# Sheet1.net
KiCad netlist of a schematic drawn in Altium Designer
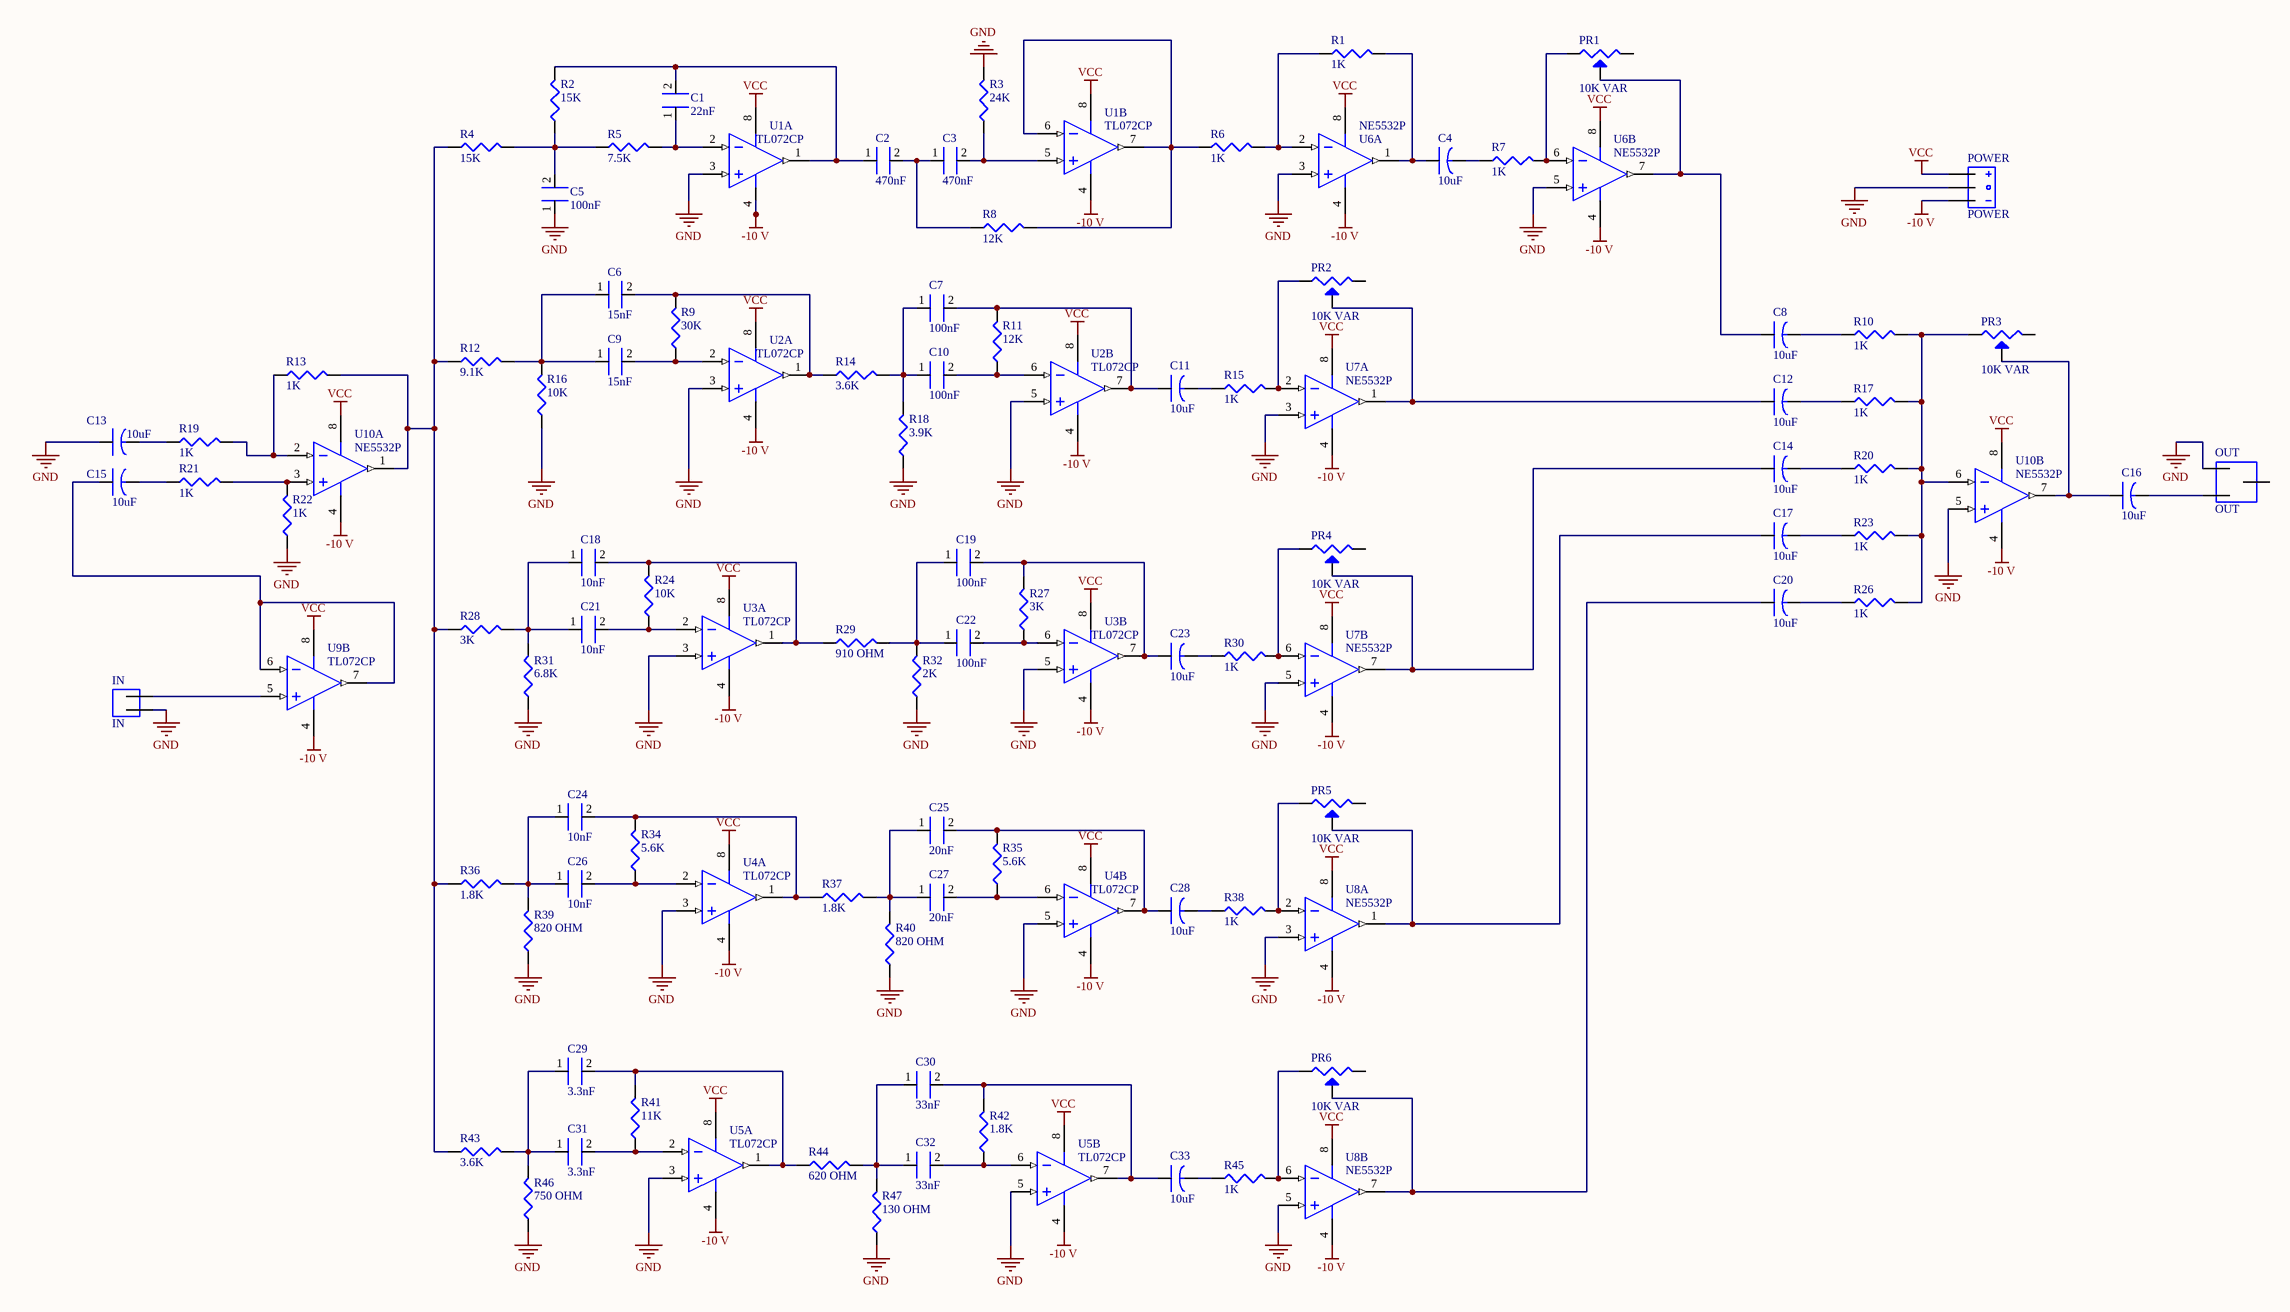
[diagram p0: Sheet1.SchDoc]

(export (version "E")
  (design (tool "Eeschema 10.0.6"))
  (components
    (comp (ref "C1")
      (value "22nF")
      (footprint "10nF")
      (fields
        (field (name "MANUFACTURER") "Nichicon")
        (field (name "MANUFACTURER PART NUMBER") "UKW1H0R1MDD1TD")
        (field (name "TOLERANCE") "20%")
      )
      (libsource (lib "Schlib1") (part "22nF"))
    )
    (comp (ref "C2")
      (value "470nF")
      (footprint "100nf")
      (fields
        (field (name "MANUFACTURER") "Nichicon")
        (field (name "MANUFACTURER PART NUMBER") "UKW1H0R1MDD1TD")
        (field (name "TOLERANCE") "20%")
      )
      (libsource (lib "Schlib1") (part "470nF"))
    )
    (comp (ref "C3")
      (value "470nF")
      (footprint "100nf")
      (fields
        (field (name "MANUFACTURER") "Nichicon")
        (field (name "MANUFACTURER PART NUMBER") "UKW1H0R1MDD1TD")
        (field (name "TOLERANCE") "20%")
      )
      (libsource (lib "Schlib1") (part "470nF"))
    )
    (comp (ref "C4")
      (value "10uF")
      (footprint "10uF")
      (description "YXF series 50V 10uF 5x11mm LS=2mm 105'C 10k HRS Aluminum Electrolytic Capacitor")
      (fields
        (field (name "MANUFACTURER") "Rubycon")
        (field (name "MANUFACTURER PART NUMBER") "50YXF10MEFC5X11")
      )
      (libsource (lib "Schlib1") (part "10uF"))
    )
    (comp (ref "C5")
      (value "100nF")
      (footprint "100nf")
      (fields
        (field (name "MANUFACTURER") "Nichicon")
        (field (name "MANUFACTURER PART NUMBER") "UKW1H0R1MDD1TD")
        (field (name "TOLERANCE") "20%")
      )
      (libsource (lib "Schlib1") (part "100nF"))
    )
    (comp (ref "C6")
      (value "15nF")
      (footprint "10nF")
      (fields
        (field (name "MANUFACTURER") "Nichicon")
        (field (name "MANUFACTURER PART NUMBER") "UKW1H0R1MDD1TD")
        (field (name "TOLERANCE") "20%")
      )
      (libsource (lib "Schlib1") (part "15nF"))
    )
    (comp (ref "C7")
      (value "100nF")
      (footprint "100nf")
      (fields
        (field (name "MANUFACTURER") "Nichicon")
        (field (name "MANUFACTURER PART NUMBER") "UKW1H0R1MDD1TD")
        (field (name "TOLERANCE") "20%")
      )
      (libsource (lib "Schlib1") (part "100nF"))
    )
    (comp (ref "C8")
      (value "10uF")
      (footprint "10uF")
      (description "YXF series 50V 10uF 5x11mm LS=2mm 105'C 10k HRS Aluminum Electrolytic Capacitor")
      (fields
        (field (name "MANUFACTURER") "Rubycon")
        (field (name "MANUFACTURER PART NUMBER") "50YXF10MEFC5X11")
      )
      (libsource (lib "Schlib1") (part "10uF"))
    )
    (comp (ref "C9")
      (value "15nF")
      (footprint "10nF")
      (fields
        (field (name "MANUFACTURER") "Nichicon")
        (field (name "MANUFACTURER PART NUMBER") "UKW1H0R1MDD1TD")
        (field (name "TOLERANCE") "20%")
      )
      (libsource (lib "Schlib1") (part "15nF"))
    )
    (comp (ref "C10")
      (value "100nF")
      (footprint "100nf")
      (fields
        (field (name "MANUFACTURER") "Nichicon")
        (field (name "MANUFACTURER PART NUMBER") "UKW1H0R1MDD1TD")
        (field (name "TOLERANCE") "20%")
      )
      (libsource (lib "Schlib1") (part "100nF"))
    )
    (comp (ref "C11")
      (value "10uF")
      (footprint "10uF")
      (description "YXF series 50V 10uF 5x11mm LS=2mm 105'C 10k HRS Aluminum Electrolytic Capacitor")
      (fields
        (field (name "MANUFACTURER") "Rubycon")
        (field (name "MANUFACTURER PART NUMBER") "50YXF10MEFC5X11")
      )
      (libsource (lib "Schlib1") (part "10uF"))
    )
    (comp (ref "C12")
      (value "10uF")
      (footprint "10uF")
      (description "YXF series 50V 10uF 5x11mm LS=2mm 105'C 10k HRS Aluminum Electrolytic Capacitor")
      (fields
        (field (name "MANUFACTURER") "Rubycon")
        (field (name "MANUFACTURER PART NUMBER") "50YXF10MEFC5X11")
      )
      (libsource (lib "Schlib1") (part "10uF"))
    )
    (comp (ref "C13")
      (value "10uF")
      (footprint "10uF")
      (description "YXF series 50V 10uF 5x11mm LS=2mm 105'C 10k HRS Aluminum Electrolytic Capacitor")
      (fields
        (field (name "MANUFACTURER") "Rubycon")
        (field (name "MANUFACTURER PART NUMBER") "50YXF10MEFC5X11")
      )
      (libsource (lib "Schlib1") (part "10uF"))
    )
    (comp (ref "C14")
      (value "10uF")
      (footprint "10uF")
      (description "YXF series 50V 10uF 5x11mm LS=2mm 105'C 10k HRS Aluminum Electrolytic Capacitor")
      (fields
        (field (name "MANUFACTURER") "Rubycon")
        (field (name "MANUFACTURER PART NUMBER") "50YXF10MEFC5X11")
      )
      (libsource (lib "Schlib1") (part "10uF"))
    )
    (comp (ref "C15")
      (value "10uF")
      (footprint "10uF")
      (description "YXF series 50V 10uF 5x11mm LS=2mm 105'C 10k HRS Aluminum Electrolytic Capacitor")
      (fields
        (field (name "MANUFACTURER") "Rubycon")
        (field (name "MANUFACTURER PART NUMBER") "50YXF10MEFC5X11")
      )
      (libsource (lib "Schlib1") (part "10uF"))
    )
    (comp (ref "C16")
      (value "10uF")
      (footprint "10uF")
      (description "YXF series 50V 10uF 5x11mm LS=2mm 105'C 10k HRS Aluminum Electrolytic Capacitor")
      (fields
        (field (name "MANUFACTURER") "Rubycon")
        (field (name "MANUFACTURER PART NUMBER") "50YXF10MEFC5X11")
      )
      (libsource (lib "Schlib1") (part "10uF"))
    )
    (comp (ref "C17")
      (value "10uF")
      (footprint "10uF")
      (description "YXF series 50V 10uF 5x11mm LS=2mm 105'C 10k HRS Aluminum Electrolytic Capacitor")
      (fields
        (field (name "MANUFACTURER") "Rubycon")
        (field (name "MANUFACTURER PART NUMBER") "50YXF10MEFC5X11")
      )
      (libsource (lib "Schlib1") (part "10uF"))
    )
    (comp (ref "C18")
      (value "10nF")
      (footprint "10nF")
      (fields
        (field (name "MANUFACTURER") "Nichicon")
        (field (name "MANUFACTURER PART NUMBER") "UKW1H0R1MDD1TD")
        (field (name "TOLERANCE") "20%")
      )
      (libsource (lib "Schlib1") (part "10nF"))
    )
    (comp (ref "C19")
      (value "100nF")
      (footprint "100nf")
      (fields
        (field (name "MANUFACTURER") "Nichicon")
        (field (name "MANUFACTURER PART NUMBER") "UKW1H0R1MDD1TD")
        (field (name "TOLERANCE") "20%")
      )
      (libsource (lib "Schlib1") (part "100nF"))
    )
    (comp (ref "C20")
      (value "10uF")
      (footprint "10uF")
      (description "YXF series 50V 10uF 5x11mm LS=2mm 105'C 10k HRS Aluminum Electrolytic Capacitor")
      (fields
        (field (name "MANUFACTURER") "Rubycon")
        (field (name "MANUFACTURER PART NUMBER") "50YXF10MEFC5X11")
      )
      (libsource (lib "Schlib1") (part "10uF"))
    )
    (comp (ref "C21")
      (value "10nF")
      (footprint "10nF")
      (fields
        (field (name "MANUFACTURER") "Nichicon")
        (field (name "MANUFACTURER PART NUMBER") "UKW1H0R1MDD1TD")
        (field (name "TOLERANCE") "20%")
      )
      (libsource (lib "Schlib1") (part "10nF"))
    )
    (comp (ref "C22")
      (value "100nF")
      (footprint "100nf")
      (fields
        (field (name "MANUFACTURER") "Nichicon")
        (field (name "MANUFACTURER PART NUMBER") "UKW1H0R1MDD1TD")
        (field (name "TOLERANCE") "20%")
      )
      (libsource (lib "Schlib1") (part "100nF"))
    )
    (comp (ref "C23")
      (value "10uF")
      (footprint "10uF")
      (description "YXF series 50V 10uF 5x11mm LS=2mm 105'C 10k HRS Aluminum Electrolytic Capacitor")
      (fields
        (field (name "MANUFACTURER") "Rubycon")
        (field (name "MANUFACTURER PART NUMBER") "50YXF10MEFC5X11")
      )
      (libsource (lib "Schlib1") (part "10uF"))
    )
    (comp (ref "C24")
      (value "10nF")
      (footprint "10nF")
      (fields
        (field (name "MANUFACTURER") "Nichicon")
        (field (name "MANUFACTURER PART NUMBER") "UKW1H0R1MDD1TD")
        (field (name "TOLERANCE") "20%")
      )
      (libsource (lib "Schlib1") (part "10nF"))
    )
    (comp (ref "C25")
      (value "20nF")
      (footprint "10nF")
      (fields
        (field (name "MANUFACTURER") "Nichicon")
        (field (name "MANUFACTURER PART NUMBER") "UKW1H0R1MDD1TD")
        (field (name "TOLERANCE") "20%")
      )
      (libsource (lib "Schlib1") (part "20nF"))
    )
    (comp (ref "C26")
      (value "10nF")
      (footprint "10nF")
      (fields
        (field (name "MANUFACTURER") "Nichicon")
        (field (name "MANUFACTURER PART NUMBER") "UKW1H0R1MDD1TD")
        (field (name "TOLERANCE") "20%")
      )
      (libsource (lib "Schlib1") (part "10nF"))
    )
    (comp (ref "C27")
      (value "20nF")
      (footprint "10nF")
      (fields
        (field (name "MANUFACTURER") "Nichicon")
        (field (name "MANUFACTURER PART NUMBER") "UKW1H0R1MDD1TD")
        (field (name "TOLERANCE") "20%")
      )
      (libsource (lib "Schlib1") (part "20nF"))
    )
    (comp (ref "C28")
      (value "10uF")
      (footprint "10uF")
      (description "YXF series 50V 10uF 5x11mm LS=2mm 105'C 10k HRS Aluminum Electrolytic Capacitor")
      (fields
        (field (name "MANUFACTURER") "Rubycon")
        (field (name "MANUFACTURER PART NUMBER") "50YXF10MEFC5X11")
      )
      (libsource (lib "Schlib1") (part "10uF"))
    )
    (comp (ref "C29")
      (value "3.3nF")
      (footprint "10nF")
      (fields
        (field (name "MANUFACTURER") "Nichicon")
        (field (name "MANUFACTURER PART NUMBER") "UKW1H0R1MDD1TD")
        (field (name "TOLERANCE") "20%")
      )
      (libsource (lib "Schlib1") (part "3.3nF"))
    )
    (comp (ref "C30")
      (value "33nF")
      (footprint "10nF")
      (fields
        (field (name "MANUFACTURER") "Nichicon")
        (field (name "MANUFACTURER PART NUMBER") "UKW1H0R1MDD1TD")
        (field (name "TOLERANCE") "20%")
      )
      (libsource (lib "Schlib1") (part "33nF"))
    )
    (comp (ref "C31")
      (value "3.3nF")
      (footprint "10nF")
      (fields
        (field (name "MANUFACTURER") "Nichicon")
        (field (name "MANUFACTURER PART NUMBER") "UKW1H0R1MDD1TD")
        (field (name "TOLERANCE") "20%")
      )
      (libsource (lib "Schlib1") (part "3.3nF"))
    )
    (comp (ref "C32")
      (value "33nF")
      (footprint "10nF")
      (fields
        (field (name "MANUFACTURER") "Nichicon")
        (field (name "MANUFACTURER PART NUMBER") "UKW1H0R1MDD1TD")
        (field (name "TOLERANCE") "20%")
      )
      (libsource (lib "Schlib1") (part "33nF"))
    )
    (comp (ref "C33")
      (value "10uF")
      (footprint "10uF")
      (description "YXF series 50V 10uF 5x11mm LS=2mm 105'C 10k HRS Aluminum Electrolytic Capacitor")
      (fields
        (field (name "MANUFACTURER") "Rubycon")
        (field (name "MANUFACTURER PART NUMBER") "50YXF10MEFC5X11")
      )
      (libsource (lib "Schlib1") (part "10uF"))
    )
    (comp (ref "IN") (value "IN") (footprint "AUDIO_IN") (libsource (lib "Schlib1") (part "A_IN")))
    (comp (ref "OUT") (value "OUT") (footprint "AUDIO_OUT") (libsource (lib "Schlib1") (part "AUDIO")))
    (comp (ref "POWER") (value "POWER") (footprint "POWER") (libsource (lib "Schlib1") (part "POWER")))
    (comp (ref "PR1") (value "10K VAR") (footprint "POT") (libsource (lib "Schlib1") (part "10K VAR")))
    (comp (ref "PR2") (value "10K VAR") (footprint "POT") (libsource (lib "Schlib1") (part "10K VAR")))
    (comp (ref "PR3") (value "10K VAR") (footprint "POT") (libsource (lib "Schlib1") (part "10K VAR")))
    (comp (ref "PR4") (value "10K VAR") (footprint "POT") (libsource (lib "Schlib1") (part "10K VAR")))
    (comp (ref "PR5") (value "10K VAR") (footprint "POT") (libsource (lib "Schlib1") (part "10K VAR")))
    (comp (ref "PR6") (value "10K VAR") (footprint "POT") (libsource (lib "Schlib1") (part "10K VAR")))
    (comp (ref "R1")
      (value "1K")
      (footprint "RESI")
      (description "RES 1K OHM 5% 1/2W AXIAL")
      (fields
        (field (name "MANUFACTURER") "Yageo")
        (field (name "MANUFACTURER PART NUMBER") "CFR-25JB-52-10K")
      )
      (libsource (lib "Schlib1") (part "1K"))
    )
    (comp (ref "R2")
      (value "15K")
      (footprint "RESI")
      (description "RES 15K OHM 5% 1/2W AXIAL")
      (fields
        (field (name "MANUFACTURER") "Yageo")
        (field (name "MANUFACTURER PART NUMBER") "CFR-25JB-52-10K")
      )
      (libsource (lib "Schlib1") (part "15K"))
    )
    (comp (ref "R3")
      (value "24K")
      (footprint "RESI")
      (description "RES 24K OHM 5% 1/2W AXIAL")
      (fields
        (field (name "MANUFACTURER") "Yageo")
        (field (name "MANUFACTURER PART NUMBER") "CFR-25JB-52-10K")
      )
      (libsource (lib "Schlib1") (part "24K"))
    )
    (comp (ref "R4")
      (value "15K")
      (footprint "RESI")
      (description "RES 15K OHM 5% 1/2W AXIAL")
      (fields
        (field (name "MANUFACTURER") "Yageo")
        (field (name "MANUFACTURER PART NUMBER") "CFR-25JB-52-10K")
      )
      (libsource (lib "Schlib1") (part "15K"))
    )
    (comp (ref "R5")
      (value "7.5K")
      (footprint "RESI")
      (description "RES 7.5K OHM 5% 1/2W AXIAL")
      (fields
        (field (name "MANUFACTURER") "Yageo")
        (field (name "MANUFACTURER PART NUMBER") "CFR-25JB-52-10K")
      )
      (libsource (lib "Schlib1") (part "7.5K"))
    )
    (comp (ref "R6")
      (value "1K")
      (footprint "RESI")
      (description "RES 1K OHM 5% 1/2W AXIAL")
      (fields
        (field (name "MANUFACTURER") "Yageo")
        (field (name "MANUFACTURER PART NUMBER") "CFR-25JB-52-10K")
      )
      (libsource (lib "Schlib1") (part "1K"))
    )
    (comp (ref "R7")
      (value "1K")
      (footprint "RESI")
      (description "RES 1K OHM 5% 1/2W AXIAL")
      (fields
        (field (name "MANUFACTURER") "Yageo")
        (field (name "MANUFACTURER PART NUMBER") "CFR-25JB-52-10K")
      )
      (libsource (lib "Schlib1") (part "1K"))
    )
    (comp (ref "R8")
      (value "12K")
      (footprint "RESI")
      (description "RES 12K OHM 5% 1/2W AXIAL")
      (fields
        (field (name "MANUFACTURER") "Yageo")
        (field (name "MANUFACTURER PART NUMBER") "CFR-25JB-52-10K")
      )
      (libsource (lib "Schlib1") (part "12K"))
    )
    (comp (ref "R9")
      (value "30K")
      (footprint "RESI")
      (description "RES 30K OHM 5% 1/2W AXIAL")
      (fields
        (field (name "MANUFACTURER") "Yageo")
        (field (name "MANUFACTURER PART NUMBER") "CFR-25JB-52-10K")
      )
      (libsource (lib "Schlib1") (part "30K"))
    )
    (comp (ref "R10")
      (value "1K")
      (footprint "RESI")
      (description "RES 1K OHM 5% 1/2W AXIAL")
      (fields
        (field (name "MANUFACTURER") "Yageo")
        (field (name "MANUFACTURER PART NUMBER") "CFR-25JB-52-10K")
      )
      (libsource (lib "Schlib1") (part "1K"))
    )
    (comp (ref "R11")
      (value "12K")
      (footprint "RESI")
      (description "RES 12K OHM 5% 1/2W AXIAL")
      (fields
        (field (name "MANUFACTURER") "Yageo")
        (field (name "MANUFACTURER PART NUMBER") "CFR-25JB-52-10K")
      )
      (libsource (lib "Schlib1") (part "12K"))
    )
    (comp (ref "R12")
      (value "9.1K")
      (footprint "RESI")
      (description "RES 9.1K OHM 5% 1/2W AXIAL")
      (fields
        (field (name "MANUFACTURER") "Yageo")
        (field (name "MANUFACTURER PART NUMBER") "CFR-25JB-52-10K")
      )
      (libsource (lib "Schlib1") (part "9.1K"))
    )
    (comp (ref "R13")
      (value "1K")
      (footprint "RESI")
      (description "RES 1K OHM 5% 1/2W AXIAL")
      (fields
        (field (name "MANUFACTURER") "Yageo")
        (field (name "MANUFACTURER PART NUMBER") "CFR-25JB-52-10K")
      )
      (libsource (lib "Schlib1") (part "1K"))
    )
    (comp (ref "R14")
      (value "3.6K")
      (footprint "RESI")
      (description "RES 3.6K OHM 5% 1/2W AXIAL")
      (fields
        (field (name "MANUFACTURER") "Yageo")
        (field (name "MANUFACTURER PART NUMBER") "CFR-25JB-52-10K")
      )
      (libsource (lib "Schlib1") (part "3.6K"))
    )
    (comp (ref "R15")
      (value "1K")
      (footprint "RESI")
      (description "RES 1K OHM 5% 1/2W AXIAL")
      (fields
        (field (name "MANUFACTURER") "Yageo")
        (field (name "MANUFACTURER PART NUMBER") "CFR-25JB-52-10K")
      )
      (libsource (lib "Schlib1") (part "1K"))
    )
    (comp (ref "R16")
      (value "10K")
      (footprint "RESI")
      (description "RES 10K OHM 5% 1/2W AXIAL")
      (fields
        (field (name "MANUFACTURER") "Yageo")
        (field (name "MANUFACTURER PART NUMBER") "CFR-25JB-52-10K")
      )
      (libsource (lib "Schlib1") (part "10K"))
    )
    (comp (ref "R17")
      (value "1K")
      (footprint "RESI")
      (description "RES 1K OHM 5% 1/2W AXIAL")
      (fields
        (field (name "MANUFACTURER") "Yageo")
        (field (name "MANUFACTURER PART NUMBER") "CFR-25JB-52-10K")
      )
      (libsource (lib "Schlib1") (part "1K"))
    )
    (comp (ref "R18")
      (value "3.9K")
      (footprint "RESI")
      (description "RES 3.9K OHM 5% 1/2W AXIAL")
      (fields
        (field (name "MANUFACTURER") "Yageo")
        (field (name "MANUFACTURER PART NUMBER") "CFR-25JB-52-10K")
      )
      (libsource (lib "Schlib1") (part "3.9K"))
    )
    (comp (ref "R19")
      (value "1K")
      (footprint "RESI")
      (description "RES 1K OHM 5% 1/2W AXIAL")
      (fields
        (field (name "MANUFACTURER") "Yageo")
        (field (name "MANUFACTURER PART NUMBER") "CFR-25JB-52-10K")
      )
      (libsource (lib "Schlib1") (part "1K"))
    )
    (comp (ref "R20")
      (value "1K")
      (footprint "RESI")
      (description "RES 1K OHM 5% 1/2W AXIAL")
      (fields
        (field (name "MANUFACTURER") "Yageo")
        (field (name "MANUFACTURER PART NUMBER") "CFR-25JB-52-10K")
      )
      (libsource (lib "Schlib1") (part "1K"))
    )
    (comp (ref "R21")
      (value "1K")
      (footprint "RESI")
      (description "RES 1K OHM 5% 1/2W AXIAL")
      (fields
        (field (name "MANUFACTURER") "Yageo")
        (field (name "MANUFACTURER PART NUMBER") "CFR-25JB-52-10K")
      )
      (libsource (lib "Schlib1") (part "1K"))
    )
    (comp (ref "R22")
      (value "1K")
      (footprint "RESI")
      (description "RES 1K OHM 5% 1/2W AXIAL")
      (fields
        (field (name "MANUFACTURER") "Yageo")
        (field (name "MANUFACTURER PART NUMBER") "CFR-25JB-52-10K")
      )
      (libsource (lib "Schlib1") (part "1K"))
    )
    (comp (ref "R23")
      (value "1K")
      (footprint "RESI")
      (description "RES 1K OHM 5% 1/2W AXIAL")
      (fields
        (field (name "MANUFACTURER") "Yageo")
        (field (name "MANUFACTURER PART NUMBER") "CFR-25JB-52-10K")
      )
      (libsource (lib "Schlib1") (part "1K"))
    )
    (comp (ref "R24")
      (value "10K")
      (footprint "RESI")
      (description "RES 10K OHM 5% 1/2W AXIAL")
      (fields
        (field (name "MANUFACTURER") "Yageo")
        (field (name "MANUFACTURER PART NUMBER") "CFR-25JB-52-10K")
      )
      (libsource (lib "Schlib1") (part "10K"))
    )
    (comp (ref "R26")
      (value "1K")
      (footprint "RESI")
      (description "RES 1K OHM 5% 1/2W AXIAL")
      (fields
        (field (name "MANUFACTURER") "Yageo")
        (field (name "MANUFACTURER PART NUMBER") "CFR-25JB-52-10K")
      )
      (libsource (lib "Schlib1") (part "1K"))
    )
    (comp (ref "R27")
      (value "3K")
      (footprint "RESI")
      (description "RES 3K OHM 5% 1/2W AXIAL")
      (fields
        (field (name "MANUFACTURER") "Yageo")
        (field (name "MANUFACTURER PART NUMBER") "CFR-25JB-52-10K")
      )
      (libsource (lib "Schlib1") (part "3K"))
    )
    (comp (ref "R28")
      (value "3K")
      (footprint "RESI")
      (description "RES 3K OHM 5% 1/2W AXIAL")
      (fields
        (field (name "MANUFACTURER") "Yageo")
        (field (name "MANUFACTURER PART NUMBER") "CFR-25JB-52-10K")
      )
      (libsource (lib "Schlib1") (part "3K"))
    )
    (comp (ref "R29")
      (value "910 OHM")
      (footprint "RESI")
      (description "RES 910 OHM 5% 1/2W AXIAL")
      (fields
        (field (name "MANUFACTURER") "Yageo")
        (field (name "MANUFACTURER PART NUMBER") "CFR-25JB-52-10K")
      )
      (libsource (lib "Schlib1") (part "910 OHM"))
    )
    (comp (ref "R30")
      (value "1K")
      (footprint "RESI")
      (description "RES 1K OHM 5% 1/2W AXIAL")
      (fields
        (field (name "MANUFACTURER") "Yageo")
        (field (name "MANUFACTURER PART NUMBER") "CFR-25JB-52-10K")
      )
      (libsource (lib "Schlib1") (part "1K"))
    )
    (comp (ref "R31")
      (value "6.8K")
      (footprint "RESI")
      (description "RES 6.8K OHM 5% 1/2W AXIAL")
      (fields
        (field (name "MANUFACTURER") "Yageo")
        (field (name "MANUFACTURER PART NUMBER") "CFR-25JB-52-10K")
      )
      (libsource (lib "Schlib1") (part "6.8K"))
    )
    (comp (ref "R32")
      (value "2K")
      (footprint "RESI")
      (description "RES 2K OHM 5% 1/2W AXIAL")
      (fields
        (field (name "MANUFACTURER") "Yageo")
        (field (name "MANUFACTURER PART NUMBER") "CFR-25JB-52-10K")
      )
      (libsource (lib "Schlib1") (part "2K"))
    )
    (comp (ref "R34")
      (value "5.6K")
      (footprint "RESI")
      (description "RES 5.6K OHM 5% 1/2W AXIAL")
      (fields
        (field (name "MANUFACTURER") "Yageo")
        (field (name "MANUFACTURER PART NUMBER") "CFR-25JB-52-10K")
      )
      (libsource (lib "Schlib1") (part "5.6K"))
    )
    (comp (ref "R35")
      (value "5.6K")
      (footprint "RESI")
      (description "RES 5.6K OHM 5% 1/2W AXIAL")
      (fields
        (field (name "MANUFACTURER") "Yageo")
        (field (name "MANUFACTURER PART NUMBER") "CFR-25JB-52-10K")
      )
      (libsource (lib "Schlib1") (part "5.6K"))
    )
    (comp (ref "R36")
      (value "1.8K")
      (footprint "RESI")
      (description "RES 1.8K OHM 5% 1/2W AXIAL")
      (fields
        (field (name "MANUFACTURER") "Yageo")
        (field (name "MANUFACTURER PART NUMBER") "CFR-25JB-52-10K")
      )
      (libsource (lib "Schlib1") (part "1.8K"))
    )
    (comp (ref "R37")
      (value "1.8K")
      (footprint "RESI")
      (description "RES 1.8K OHM 5% 1/2W AXIAL")
      (fields
        (field (name "MANUFACTURER") "Yageo")
        (field (name "MANUFACTURER PART NUMBER") "CFR-25JB-52-10K")
      )
      (libsource (lib "Schlib1") (part "1.8K"))
    )
    (comp (ref "R38")
      (value "1K")
      (footprint "RESI")
      (description "RES 1K OHM 5% 1/2W AXIAL")
      (fields
        (field (name "MANUFACTURER") "Yageo")
        (field (name "MANUFACTURER PART NUMBER") "CFR-25JB-52-10K")
      )
      (libsource (lib "Schlib1") (part "1K"))
    )
    (comp (ref "R39")
      (value "820 OHM")
      (footprint "RESI")
      (description "RES 820 OHM 5% 1/2W AXIAL")
      (fields
        (field (name "MANUFACTURER") "Yageo")
        (field (name "MANUFACTURER PART NUMBER") "CFR-25JB-52-10K")
      )
      (libsource (lib "Schlib1") (part "820 OHM"))
    )
    (comp (ref "R40")
      (value "820 OHM")
      (footprint "RESI")
      (description "RES 820 OHM 5% 1/2W AXIAL")
      (fields
        (field (name "MANUFACTURER") "Yageo")
        (field (name "MANUFACTURER PART NUMBER") "CFR-25JB-52-10K")
      )
      (libsource (lib "Schlib1") (part "820 OHM"))
    )
    (comp (ref "R41")
      (value "11K")
      (footprint "RESI")
      (description "RES 11K OHM 5% 1/2W AXIAL")
      (fields
        (field (name "MANUFACTURER") "Yageo")
        (field (name "MANUFACTURER PART NUMBER") "CFR-25JB-52-10K")
      )
      (libsource (lib "Schlib1") (part "11K"))
    )
    (comp (ref "R42")
      (value "1.8K")
      (footprint "RESI")
      (description "RES 1.8K OHM 5% 1/2W AXIAL")
      (fields
        (field (name "MANUFACTURER") "Yageo")
        (field (name "MANUFACTURER PART NUMBER") "CFR-25JB-52-10K")
      )
      (libsource (lib "Schlib1") (part "1.8K"))
    )
    (comp (ref "R43")
      (value "3.6K")
      (footprint "RESI")
      (description "RES 3.6K OHM 5% 1/2W AXIAL")
      (fields
        (field (name "MANUFACTURER") "Yageo")
        (field (name "MANUFACTURER PART NUMBER") "CFR-25JB-52-10K")
      )
      (libsource (lib "Schlib1") (part "3.6K"))
    )
    (comp (ref "R44")
      (value "620 OHM")
      (footprint "RESI")
      (description "RES 620 OHM 5% 1/2W AXIAL")
      (fields
        (field (name "MANUFACTURER") "Yageo")
        (field (name "MANUFACTURER PART NUMBER") "CFR-25JB-52-10K")
      )
      (libsource (lib "Schlib1") (part "620 OHM"))
    )
    (comp (ref "R45")
      (value "1K")
      (footprint "RESI")
      (description "RES 1K OHM 5% 1/2W AXIAL")
      (fields
        (field (name "MANUFACTURER") "Yageo")
        (field (name "MANUFACTURER PART NUMBER") "CFR-25JB-52-10K")
      )
      (libsource (lib "Schlib1") (part "1K"))
    )
    (comp (ref "R46")
      (value "750 OHM")
      (footprint "RESI")
      (description "RES 750 OHM 5% 1/2W AXIAL")
      (fields
        (field (name "MANUFACTURER") "Yageo")
        (field (name "MANUFACTURER PART NUMBER") "CFR-25JB-52-10K")
      )
      (libsource (lib "Schlib1") (part "750 OHM"))
    )
    (comp (ref "R47")
      (value "130 OHM")
      (footprint "RESI")
      (description "RES 130 OHM 5% 1/2W AXIAL")
      (fields
        (field (name "MANUFACTURER") "Yageo")
        (field (name "MANUFACTURER PART NUMBER") "CFR-25JB-52-10K")
      )
      (libsource (lib "Schlib1") (part "130 OHM"))
    )
    (comp (ref "U1")
      (value "TL072CP")
      (footprint "TL0072CP")
      (fields (field (name "MANUFACTURER") "Texas Instruments"))
      (libsource (lib "Schlib1") (part "TL072CP"))
    )
    (comp (ref "U2")
      (value "TL072CP")
      (footprint "TL0072CP")
      (fields (field (name "MANUFACTURER") "Texas Instruments"))
      (libsource (lib "Schlib1") (part "TL072CP"))
    )
    (comp (ref "U3")
      (value "TL072CP")
      (footprint "TL0072CP")
      (fields (field (name "MANUFACTURER") "Texas Instruments"))
      (libsource (lib "Schlib1") (part "TL072CP"))
    )
    (comp (ref "U4")
      (value "TL072CP")
      (footprint "TL0072CP")
      (fields (field (name "MANUFACTURER") "Texas Instruments"))
      (libsource (lib "Schlib1") (part "TL072CP"))
    )
    (comp (ref "U5")
      (value "TL072CP")
      (footprint "TL0072CP")
      (fields (field (name "MANUFACTURER") "Texas Instruments"))
      (libsource (lib "Schlib1") (part "TL072CP"))
    )
    (comp (ref "U6")
      (value "NE5532P")
      (footprint "NE5532P")
      (fields (field (name "MANUFACTURER") "Texas Instruments"))
      (libsource (lib "Schlib1") (part "NE5532P"))
    )
    (comp (ref "U7")
      (value "NE5532P")
      (footprint "NE5532P")
      (fields (field (name "MANUFACTURER") "Texas Instruments"))
      (libsource (lib "Schlib1") (part "NE5532P"))
    )
    (comp (ref "U8")
      (value "NE5532P")
      (footprint "NE5532P")
      (fields (field (name "MANUFACTURER") "Texas Instruments"))
      (libsource (lib "Schlib1") (part "NE5532P"))
    )
    (comp (ref "U9")
      (value "TL072CP")
      (footprint "TL0072CP")
      (fields (field (name "MANUFACTURER") "Texas Instruments"))
      (libsource (lib "Schlib1") (part "TL072CP"))
    )
    (comp (ref "U10")
      (value "NE5532P")
      (footprint "NE5532P")
      (fields (field (name "MANUFACTURER") "Texas Instruments"))
      (libsource (lib "Schlib1") (part "NE5532P"))
    )
  )
  (nets
    (net (code "1") (name "-10 V") (class "Default")
      (node (ref "POWER") (pin "3") (pinfunction "3_3") (pintype "power_in"))
      (node (ref "U1") (pin "4") (pinfunction "VCC-_4") (pintype "power_in"))
      (node (ref "U10") (pin "4") (pinfunction "VCC-_4") (pintype "power_in"))
      (node (ref "U2") (pin "4") (pinfunction "VCC-_4") (pintype "power_in"))
      (node (ref "U3") (pin "4") (pinfunction "VCC-_4") (pintype "power_in"))
      (node (ref "U4") (pin "4") (pinfunction "VCC-_4") (pintype "power_in"))
      (node (ref "U5") (pin "4") (pinfunction "VCC-_4") (pintype "power_in"))
      (node (ref "U6") (pin "4") (pinfunction "VCC-_4") (pintype "power_in"))
      (node (ref "U7") (pin "4") (pinfunction "VCC-_4") (pintype "power_in"))
      (node (ref "U8") (pin "4") (pinfunction "VCC-_4") (pintype "power_in"))
      (node (ref "U9") (pin "4") (pinfunction "VCC-_4") (pintype "power_in"))
    )
    (net (code "2") (name "GND") (class "Default")
      (node (ref "C13") (pin "1") (pinfunction "1_1") (pintype "passive"))
      (node (ref "C5") (pin "1") (pinfunction "1_1") (pintype "passive"))
      (node (ref "IN") (pin "1") (pinfunction "1_1") (pintype "passive"))
      (node (ref "OUT") (pin "2") (pinfunction "2_2") (pintype "passive"))
      (node (ref "POWER") (pin "2") (pinfunction "2_2") (pintype "power_in"))
      (node (ref "R16") (pin "1") (pinfunction "1_1") (pintype "passive"))
      (node (ref "R18") (pin "1") (pinfunction "1_1") (pintype "passive"))
      (node (ref "R22") (pin "1") (pinfunction "1_1") (pintype "passive"))
      (node (ref "R3") (pin "2") (pinfunction "2_2") (pintype "passive"))
      (node (ref "R31") (pin "1") (pinfunction "1_1") (pintype "passive"))
      (node (ref "R32") (pin "1") (pinfunction "1_1") (pintype "passive"))
      (node (ref "R39") (pin "1") (pinfunction "1_1") (pintype "passive"))
      (node (ref "R40") (pin "1") (pinfunction "1_1") (pintype "passive"))
      (node (ref "R46") (pin "1") (pinfunction "1_1") (pintype "passive"))
      (node (ref "R47") (pin "1") (pinfunction "1_1") (pintype "passive"))
      (node (ref "U1") (pin "3") (pinfunction "IN1+_3") (pintype "input"))
      (node (ref "U10") (pin "5") (pinfunction "IN2+_5") (pintype "input"))
      (node (ref "U2") (pin "3") (pinfunction "IN1+_3") (pintype "input"))
      (node (ref "U2") (pin "5") (pinfunction "IN2+_5") (pintype "input"))
      (node (ref "U3") (pin "3") (pinfunction "IN1+_3") (pintype "input"))
      (node (ref "U3") (pin "5") (pinfunction "IN2+_5") (pintype "input"))
      (node (ref "U4") (pin "3") (pinfunction "IN1+_3") (pintype "input"))
      (node (ref "U4") (pin "5") (pinfunction "IN2+_5") (pintype "input"))
      (node (ref "U5") (pin "3") (pinfunction "IN1+_3") (pintype "input"))
      (node (ref "U5") (pin "5") (pinfunction "IN2+_5") (pintype "input"))
      (node (ref "U6") (pin "3") (pinfunction "IN1+_3") (pintype "input"))
      (node (ref "U6") (pin "5") (pinfunction "IN2+_5") (pintype "input"))
      (node (ref "U7") (pin "3") (pinfunction "IN1+_3") (pintype "input"))
      (node (ref "U7") (pin "5") (pinfunction "IN2+_5") (pintype "input"))
      (node (ref "U8") (pin "3") (pinfunction "IN1+_3") (pintype "input"))
      (node (ref "U8") (pin "5") (pinfunction "IN2+_5") (pintype "input"))
    )
    (net (code "3") (name "Net-(C2-Pad2)") (class "Default")
      (node (ref "C2") (pin "2") (pinfunction "2_2") (pintype "passive"))
      (node (ref "C3") (pin "1") (pinfunction "1_1") (pintype "passive"))
      (node (ref "R8") (pin "1") (pinfunction "1_1") (pintype "passive"))
    )
    (net (code "4") (name "Net-(C4-Pad2)") (class "Default")
      (node (ref "C4") (pin "2") (pinfunction "2_2") (pintype "passive"))
      (node (ref "R7") (pin "1") (pinfunction "1_1") (pintype "passive"))
    )
    (net (code "5") (name "Net-(C5-Pad2)") (class "Default")
      (node (ref "C5") (pin "2") (pinfunction "2_2") (pintype "passive"))
      (node (ref "R2") (pin "1") (pinfunction "1_1") (pintype "passive"))
      (node (ref "R4") (pin "2") (pinfunction "2_2") (pintype "passive"))
      (node (ref "R5") (pin "1") (pinfunction "1_1") (pintype "passive"))
    )
    (net (code "6") (name "Net-(C6-Pad1)") (class "Default")
      (node (ref "C6") (pin "1") (pinfunction "1_1") (pintype "passive"))
      (node (ref "C9") (pin "1") (pinfunction "1_1") (pintype "passive"))
      (node (ref "R12") (pin "2") (pinfunction "2_2") (pintype "passive"))
      (node (ref "R16") (pin "2") (pinfunction "2_2") (pintype "passive"))
    )
    (net (code "7") (name "Net-(C8-Pad2)") (class "Default")
      (node (ref "C8") (pin "2") (pinfunction "2_2") (pintype "passive"))
      (node (ref "R10") (pin "1") (pinfunction "1_1") (pintype "passive"))
    )
    (net (code "8") (name "Net-(C10-Pad1)") (class "Default")
      (node (ref "C10") (pin "1") (pinfunction "1_1") (pintype "passive"))
      (node (ref "C7") (pin "1") (pinfunction "1_1") (pintype "passive"))
      (node (ref "R14") (pin "2") (pinfunction "2_2") (pintype "passive"))
      (node (ref "R18") (pin "2") (pinfunction "2_2") (pintype "passive"))
    )
    (net (code "9") (name "Net-(C11-Pad2)") (class "Default")
      (node (ref "C11") (pin "2") (pinfunction "2_2") (pintype "passive"))
      (node (ref "R15") (pin "1") (pinfunction "1_1") (pintype "passive"))
    )
    (net (code "10") (name "Net-(C12-Pad2)") (class "Default")
      (node (ref "C12") (pin "2") (pinfunction "2_2") (pintype "passive"))
      (node (ref "R17") (pin "1") (pinfunction "1_1") (pintype "passive"))
    )
    (net (code "11") (name "Net-(C13-Pad2)") (class "Default")
      (node (ref "C13") (pin "2") (pinfunction "2_2") (pintype "passive"))
      (node (ref "R19") (pin "1") (pinfunction "1_1") (pintype "passive"))
    )
    (net (code "12") (name "Net-(C14-Pad2)") (class "Default")
      (node (ref "C14") (pin "2") (pinfunction "2_2") (pintype "passive"))
      (node (ref "R20") (pin "1") (pinfunction "1_1") (pintype "passive"))
    )
    (net (code "13") (name "Net-(C15-Pad2)") (class "Default")
      (node (ref "C15") (pin "2") (pinfunction "2_2") (pintype "passive"))
      (node (ref "R21") (pin "1") (pinfunction "1_1") (pintype "passive"))
    )
    (net (code "14") (name "Net-(C16-Pad2)") (class "Default")
      (node (ref "C16") (pin "2") (pinfunction "2_2") (pintype "passive"))
      (node (ref "OUT") (pin "3") (pinfunction "3_3") (pintype "passive"))
    )
    (net (code "15") (name "Net-(C17-Pad2)") (class "Default")
      (node (ref "C17") (pin "2") (pinfunction "2_2") (pintype "passive"))
      (node (ref "R23") (pin "1") (pinfunction "1_1") (pintype "passive"))
    )
    (net (code "16") (name "Net-(C18-Pad1)") (class "Default")
      (node (ref "C18") (pin "1") (pinfunction "1_1") (pintype "passive"))
      (node (ref "C21") (pin "1") (pinfunction "1_1") (pintype "passive"))
      (node (ref "R28") (pin "2") (pinfunction "2_2") (pintype "passive"))
      (node (ref "R31") (pin "2") (pinfunction "2_2") (pintype "passive"))
    )
    (net (code "17") (name "Net-(C19-Pad1)") (class "Default")
      (node (ref "C19") (pin "1") (pinfunction "1_1") (pintype "passive"))
      (node (ref "C22") (pin "1") (pinfunction "1_1") (pintype "passive"))
      (node (ref "R29") (pin "2") (pinfunction "2_2") (pintype "passive"))
      (node (ref "R32") (pin "2") (pinfunction "2_2") (pintype "passive"))
    )
    (net (code "18") (name "Net-(C20-Pad2)") (class "Default")
      (node (ref "C20") (pin "2") (pinfunction "2_2") (pintype "passive"))
      (node (ref "R26") (pin "1") (pinfunction "1_1") (pintype "passive"))
    )
    (net (code "19") (name "Net-(C23-Pad2)") (class "Default")
      (node (ref "C23") (pin "2") (pinfunction "2_2") (pintype "passive"))
      (node (ref "R30") (pin "1") (pinfunction "1_1") (pintype "passive"))
    )
    (net (code "20") (name "Net-(C24-Pad1)") (class "Default")
      (node (ref "C24") (pin "1") (pinfunction "1_1") (pintype "passive"))
      (node (ref "C26") (pin "1") (pinfunction "1_1") (pintype "passive"))
      (node (ref "R36") (pin "2") (pinfunction "2_2") (pintype "passive"))
      (node (ref "R39") (pin "2") (pinfunction "2_2") (pintype "passive"))
    )
    (net (code "21") (name "Net-(C25-Pad1)") (class "Default")
      (node (ref "C25") (pin "1") (pinfunction "1_1") (pintype "passive"))
      (node (ref "C27") (pin "1") (pinfunction "1_1") (pintype "passive"))
      (node (ref "R37") (pin "2") (pinfunction "2_2") (pintype "passive"))
      (node (ref "R40") (pin "2") (pinfunction "2_2") (pintype "passive"))
    )
    (net (code "22") (name "Net-(C28-Pad2)") (class "Default")
      (node (ref "C28") (pin "2") (pinfunction "2_2") (pintype "passive"))
      (node (ref "R38") (pin "1") (pinfunction "1_1") (pintype "passive"))
    )
    (net (code "23") (name "Net-(C29-Pad1)") (class "Default")
      (node (ref "C29") (pin "1") (pinfunction "1_1") (pintype "passive"))
      (node (ref "C31") (pin "1") (pinfunction "1_1") (pintype "passive"))
      (node (ref "R43") (pin "2") (pinfunction "2_2") (pintype "passive"))
      (node (ref "R46") (pin "2") (pinfunction "2_2") (pintype "passive"))
    )
    (net (code "24") (name "Net-(C30-Pad1)") (class "Default")
      (node (ref "C30") (pin "1") (pinfunction "1_1") (pintype "passive"))
      (node (ref "C32") (pin "1") (pinfunction "1_1") (pintype "passive"))
      (node (ref "R44") (pin "2") (pinfunction "2_2") (pintype "passive"))
      (node (ref "R47") (pin "2") (pinfunction "2_2") (pintype "passive"))
    )
    (net (code "25") (name "Net-(C33-Pad2)") (class "Default")
      (node (ref "C33") (pin "2") (pinfunction "2_2") (pintype "passive"))
      (node (ref "R45") (pin "1") (pinfunction "1_1") (pintype "passive"))
    )
    (net (code "26") (name "Net-(U1A-IN1-)") (class "Default")
      (node (ref "C1") (pin "1") (pinfunction "1_1") (pintype "passive"))
      (node (ref "R5") (pin "2") (pinfunction "2_2") (pintype "passive"))
      (node (ref "U1") (pin "2") (pinfunction "IN1-_2") (pintype "input"))
    )
    (net (code "27") (name "Net-(U1A-OUT1)") (class "Default")
      (node (ref "C1") (pin "2") (pinfunction "2_2") (pintype "passive"))
      (node (ref "C2") (pin "1") (pinfunction "1_1") (pintype "passive"))
      (node (ref "R2") (pin "2") (pinfunction "2_2") (pintype "passive"))
      (node (ref "U1") (pin "1") (pinfunction "OUT1_1") (pintype "output"))
    )
    (net (code "28") (name "Net-(U1B-IN2+)") (class "Default")
      (node (ref "C3") (pin "2") (pinfunction "2_2") (pintype "passive"))
      (node (ref "R3") (pin "1") (pinfunction "1_1") (pintype "passive"))
      (node (ref "U1") (pin "5") (pinfunction "IN2+_5") (pintype "input"))
    )
    (net (code "29") (name "Net-(U1B-IN2-)") (class "Default")
      (node (ref "R6") (pin "1") (pinfunction "1_1") (pintype "passive"))
      (node (ref "R8") (pin "2") (pinfunction "2_2") (pintype "passive"))
      (node (ref "U1") (pin "6") (pinfunction "IN2-_6") (pintype "input"))
      (node (ref "U1") (pin "7") (pinfunction "OUT2_7") (pintype "output"))
    )
    (net (code "30") (name "Net-(U2A-IN1-)") (class "Default")
      (node (ref "C9") (pin "2") (pinfunction "2_2") (pintype "passive"))
      (node (ref "R9") (pin "1") (pinfunction "1_1") (pintype "passive"))
      (node (ref "U2") (pin "2") (pinfunction "IN1-_2") (pintype "input"))
    )
    (net (code "31") (name "Net-(U2A-OUT1)") (class "Default")
      (node (ref "C6") (pin "2") (pinfunction "2_2") (pintype "passive"))
      (node (ref "R14") (pin "1") (pinfunction "1_1") (pintype "passive"))
      (node (ref "R9") (pin "2") (pinfunction "2_2") (pintype "passive"))
      (node (ref "U2") (pin "1") (pinfunction "OUT1_1") (pintype "output"))
    )
    (net (code "32") (name "Net-(U2B-IN2-)") (class "Default")
      (node (ref "C10") (pin "2") (pinfunction "2_2") (pintype "passive"))
      (node (ref "R11") (pin "1") (pinfunction "1_1") (pintype "passive"))
      (node (ref "U2") (pin "6") (pinfunction "IN2-_6") (pintype "input"))
    )
    (net (code "33") (name "Net-(U2B-OUT2)") (class "Default")
      (node (ref "C11") (pin "1") (pinfunction "1_1") (pintype "passive"))
      (node (ref "C7") (pin "2") (pinfunction "2_2") (pintype "passive"))
      (node (ref "R11") (pin "2") (pinfunction "2_2") (pintype "passive"))
      (node (ref "U2") (pin "7") (pinfunction "OUT2_7") (pintype "output"))
    )
    (net (code "34") (name "Net-(U3A-IN1-)") (class "Default")
      (node (ref "C21") (pin "2") (pinfunction "2_2") (pintype "passive"))
      (node (ref "R24") (pin "1") (pinfunction "1_1") (pintype "passive"))
      (node (ref "U3") (pin "2") (pinfunction "IN1-_2") (pintype "input"))
    )
    (net (code "35") (name "Net-(U3A-OUT1)") (class "Default")
      (node (ref "C18") (pin "2") (pinfunction "2_2") (pintype "passive"))
      (node (ref "R24") (pin "2") (pinfunction "2_2") (pintype "passive"))
      (node (ref "R29") (pin "1") (pinfunction "1_1") (pintype "passive"))
      (node (ref "U3") (pin "1") (pinfunction "OUT1_1") (pintype "output"))
    )
    (net (code "36") (name "Net-(U3B-IN2-)") (class "Default")
      (node (ref "C22") (pin "2") (pinfunction "2_2") (pintype "passive"))
      (node (ref "R27") (pin "1") (pinfunction "1_1") (pintype "passive"))
      (node (ref "U3") (pin "6") (pinfunction "IN2-_6") (pintype "input"))
    )
    (net (code "37") (name "Net-(U3B-OUT2)") (class "Default")
      (node (ref "C19") (pin "2") (pinfunction "2_2") (pintype "passive"))
      (node (ref "C23") (pin "1") (pinfunction "1_1") (pintype "passive"))
      (node (ref "R27") (pin "2") (pinfunction "2_2") (pintype "passive"))
      (node (ref "U3") (pin "7") (pinfunction "OUT2_7") (pintype "output"))
    )
    (net (code "38") (name "Net-(U4A-IN1-)") (class "Default")
      (node (ref "C26") (pin "2") (pinfunction "2_2") (pintype "passive"))
      (node (ref "R34") (pin "1") (pinfunction "1_1") (pintype "passive"))
      (node (ref "U4") (pin "2") (pinfunction "IN1-_2") (pintype "input"))
    )
    (net (code "39") (name "Net-(U4A-OUT1)") (class "Default")
      (node (ref "C24") (pin "2") (pinfunction "2_2") (pintype "passive"))
      (node (ref "R34") (pin "2") (pinfunction "2_2") (pintype "passive"))
      (node (ref "R37") (pin "1") (pinfunction "1_1") (pintype "passive"))
      (node (ref "U4") (pin "1") (pinfunction "OUT1_1") (pintype "output"))
    )
    (net (code "40") (name "Net-(U4B-IN2-)") (class "Default")
      (node (ref "C27") (pin "2") (pinfunction "2_2") (pintype "passive"))
      (node (ref "R35") (pin "1") (pinfunction "1_1") (pintype "passive"))
      (node (ref "U4") (pin "6") (pinfunction "IN2-_6") (pintype "input"))
    )
    (net (code "41") (name "Net-(U4B-OUT2)") (class "Default")
      (node (ref "C25") (pin "2") (pinfunction "2_2") (pintype "passive"))
      (node (ref "C28") (pin "1") (pinfunction "1_1") (pintype "passive"))
      (node (ref "R35") (pin "2") (pinfunction "2_2") (pintype "passive"))
      (node (ref "U4") (pin "7") (pinfunction "OUT2_7") (pintype "output"))
    )
    (net (code "42") (name "Net-(U5A-IN1-)") (class "Default")
      (node (ref "C31") (pin "2") (pinfunction "2_2") (pintype "passive"))
      (node (ref "R41") (pin "1") (pinfunction "1_1") (pintype "passive"))
      (node (ref "U5") (pin "2") (pinfunction "IN1-_2") (pintype "input"))
    )
    (net (code "43") (name "Net-(U5A-OUT1)") (class "Default")
      (node (ref "C29") (pin "2") (pinfunction "2_2") (pintype "passive"))
      (node (ref "R41") (pin "2") (pinfunction "2_2") (pintype "passive"))
      (node (ref "R44") (pin "1") (pinfunction "1_1") (pintype "passive"))
      (node (ref "U5") (pin "1") (pinfunction "OUT1_1") (pintype "output"))
    )
    (net (code "44") (name "Net-(U5B-IN2-)") (class "Default")
      (node (ref "C32") (pin "2") (pinfunction "2_2") (pintype "passive"))
      (node (ref "R42") (pin "1") (pinfunction "1_1") (pintype "passive"))
      (node (ref "U5") (pin "6") (pinfunction "IN2-_6") (pintype "input"))
    )
    (net (code "45") (name "Net-(U5B-OUT2)") (class "Default")
      (node (ref "C30") (pin "2") (pinfunction "2_2") (pintype "passive"))
      (node (ref "C33") (pin "1") (pinfunction "1_1") (pintype "passive"))
      (node (ref "R42") (pin "2") (pinfunction "2_2") (pintype "passive"))
      (node (ref "U5") (pin "7") (pinfunction "OUT2_7") (pintype "output"))
    )
    (net (code "46") (name "Net-(U6A-IN1-)") (class "Default")
      (node (ref "R1") (pin "1") (pinfunction "1_1") (pintype "passive"))
      (node (ref "R6") (pin "2") (pinfunction "2_2") (pintype "passive"))
      (node (ref "U6") (pin "2") (pinfunction "IN1-_2") (pintype "input"))
    )
    (net (code "47") (name "Net-(U6A-OUT1)") (class "Default")
      (node (ref "C4") (pin "1") (pinfunction "1_1") (pintype "passive"))
      (node (ref "R1") (pin "2") (pinfunction "2_2") (pintype "passive"))
      (node (ref "U6") (pin "1") (pinfunction "OUT1_1") (pintype "output"))
    )
    (net (code "48") (name "Net-(U6B-IN2-)") (class "Default")
      (node (ref "PR1") (pin "1") (pinfunction "1_1") (pintype "passive"))
      (node (ref "R7") (pin "2") (pinfunction "2_2") (pintype "passive"))
      (node (ref "U6") (pin "6") (pinfunction "IN2-_6") (pintype "input"))
    )
    (net (code "49") (name "Net-(U6B-OUT2)") (class "Default")
      (node (ref "C8") (pin "1") (pinfunction "1_1") (pintype "passive"))
      (node (ref "PR1") (pin "2") (pinfunction "2_2") (pintype "passive"))
      (node (ref "U6") (pin "7") (pinfunction "OUT2_7") (pintype "output"))
    )
    (net (code "50") (name "Net-(U7A-IN1-)") (class "Default")
      (node (ref "PR2") (pin "1") (pinfunction "1_1") (pintype "passive"))
      (node (ref "R15") (pin "2") (pinfunction "2_2") (pintype "passive"))
      (node (ref "U7") (pin "2") (pinfunction "IN1-_2") (pintype "input"))
    )
    (net (code "51") (name "Net-(U7A-OUT1)") (class "Default")
      (node (ref "C12") (pin "1") (pinfunction "1_1") (pintype "passive"))
      (node (ref "PR2") (pin "2") (pinfunction "2_2") (pintype "passive"))
      (node (ref "U7") (pin "1") (pinfunction "OUT1_1") (pintype "output"))
    )
    (net (code "52") (name "Net-(U7B-IN2-)") (class "Default")
      (node (ref "PR4") (pin "1") (pinfunction "1_1") (pintype "passive"))
      (node (ref "R30") (pin "2") (pinfunction "2_2") (pintype "passive"))
      (node (ref "U7") (pin "6") (pinfunction "IN2-_6") (pintype "input"))
    )
    (net (code "53") (name "Net-(U7B-OUT2)") (class "Default")
      (node (ref "C14") (pin "1") (pinfunction "1_1") (pintype "passive"))
      (node (ref "PR4") (pin "2") (pinfunction "2_2") (pintype "passive"))
      (node (ref "U7") (pin "7") (pinfunction "OUT2_7") (pintype "output"))
    )
    (net (code "54") (name "Net-(U8A-IN1-)") (class "Default")
      (node (ref "PR5") (pin "1") (pinfunction "1_1") (pintype "passive"))
      (node (ref "R38") (pin "2") (pinfunction "2_2") (pintype "passive"))
      (node (ref "U8") (pin "2") (pinfunction "IN1-_2") (pintype "input"))
    )
    (net (code "55") (name "Net-(U8A-OUT1)") (class "Default")
      (node (ref "C17") (pin "1") (pinfunction "1_1") (pintype "passive"))
      (node (ref "PR5") (pin "2") (pinfunction "2_2") (pintype "passive"))
      (node (ref "U8") (pin "1") (pinfunction "OUT1_1") (pintype "output"))
    )
    (net (code "56") (name "Net-(U8B-IN2-)") (class "Default")
      (node (ref "PR6") (pin "1") (pinfunction "1_1") (pintype "passive"))
      (node (ref "R45") (pin "2") (pinfunction "2_2") (pintype "passive"))
      (node (ref "U8") (pin "6") (pinfunction "IN2-_6") (pintype "input"))
    )
    (net (code "57") (name "Net-(U8B-OUT2)") (class "Default")
      (node (ref "C20") (pin "1") (pinfunction "1_1") (pintype "passive"))
      (node (ref "PR6") (pin "2") (pinfunction "2_2") (pintype "passive"))
      (node (ref "U8") (pin "7") (pinfunction "OUT2_7") (pintype "output"))
    )
    (net (code "58") (name "Net-(U9B-IN2+)") (class "Default")
      (node (ref "IN") (pin "2") (pinfunction "2_2") (pintype "passive"))
      (node (ref "U9") (pin "5") (pinfunction "IN2+_5") (pintype "input"))
    )
    (net (code "59") (name "Net-(U9B-IN2-)") (class "Default")
      (node (ref "C15") (pin "1") (pinfunction "1_1") (pintype "passive"))
      (node (ref "U9") (pin "6") (pinfunction "IN2-_6") (pintype "input"))
      (node (ref "U9") (pin "7") (pinfunction "OUT2_7") (pintype "output"))
    )
    (net (code "60") (name "Net-(U10A-IN1+)") (class "Default")
      (node (ref "R21") (pin "2") (pinfunction "2_2") (pintype "passive"))
      (node (ref "R22") (pin "2") (pinfunction "2_2") (pintype "passive"))
      (node (ref "U10") (pin "3") (pinfunction "IN1+_3") (pintype "input"))
    )
    (net (code "61") (name "Net-(U10A-IN1-)") (class "Default")
      (node (ref "R13") (pin "1") (pinfunction "1_1") (pintype "passive"))
      (node (ref "R19") (pin "2") (pinfunction "2_2") (pintype "passive"))
      (node (ref "U10") (pin "2") (pinfunction "IN1-_2") (pintype "input"))
    )
    (net (code "62") (name "Net-(U10A-OUT1)") (class "Default")
      (node (ref "R12") (pin "1") (pinfunction "1_1") (pintype "passive"))
      (node (ref "R13") (pin "2") (pinfunction "2_2") (pintype "passive"))
      (node (ref "R28") (pin "1") (pinfunction "1_1") (pintype "passive"))
      (node (ref "R36") (pin "1") (pinfunction "1_1") (pintype "passive"))
      (node (ref "R4") (pin "1") (pinfunction "1_1") (pintype "passive"))
      (node (ref "R43") (pin "1") (pinfunction "1_1") (pintype "passive"))
      (node (ref "U10") (pin "1") (pinfunction "OUT1_1") (pintype "output"))
    )
    (net (code "63") (name "Net-(U10B-IN2-)") (class "Default")
      (node (ref "PR3") (pin "1") (pinfunction "1_1") (pintype "passive"))
      (node (ref "R10") (pin "2") (pinfunction "2_2") (pintype "passive"))
      (node (ref "R17") (pin "2") (pinfunction "2_2") (pintype "passive"))
      (node (ref "R20") (pin "2") (pinfunction "2_2") (pintype "passive"))
      (node (ref "R23") (pin "2") (pinfunction "2_2") (pintype "passive"))
      (node (ref "R26") (pin "2") (pinfunction "2_2") (pintype "passive"))
      (node (ref "U10") (pin "6") (pinfunction "IN2-_6") (pintype "input"))
    )
    (net (code "64") (name "Net-(U10B-OUT2)") (class "Default")
      (node (ref "C16") (pin "1") (pinfunction "1_1") (pintype "passive"))
      (node (ref "PR3") (pin "2") (pinfunction "2_2") (pintype "passive"))
      (node (ref "U10") (pin "7") (pinfunction "OUT2_7") (pintype "output"))
    )
    (net (code "65") (name "VCC") (class "Default")
      (node (ref "POWER") (pin "1") (pinfunction "1_1") (pintype "power_in"))
      (node (ref "U1") (pin "8") (pinfunction "VCC+_8") (pintype "power_in"))
      (node (ref "U10") (pin "8") (pinfunction "VCC+_8") (pintype "power_in"))
      (node (ref "U2") (pin "8") (pinfunction "VCC+_8") (pintype "power_in"))
      (node (ref "U3") (pin "8") (pinfunction "VCC+_8") (pintype "power_in"))
      (node (ref "U4") (pin "8") (pinfunction "VCC+_8") (pintype "power_in"))
      (node (ref "U5") (pin "8") (pinfunction "VCC+_8") (pintype "power_in"))
      (node (ref "U6") (pin "8") (pinfunction "VCC+_8") (pintype "power_in"))
      (node (ref "U7") (pin "8") (pinfunction "VCC+_8") (pintype "power_in"))
      (node (ref "U8") (pin "8") (pinfunction "VCC+_8") (pintype "power_in"))
      (node (ref "U9") (pin "8") (pinfunction "VCC+_8") (pintype "power_in"))
    )
    (net (code "66") (name "unconnected-(OUT-Pad1)") (class "Default")
      (node (ref "OUT") (pin "1") (pinfunction "1_1") (pintype "passive"))
    )
    (net (code "67") (name "unconnected-(PR1-Pad3)") (class "Default")
      (node (ref "PR1") (pin "3") (pinfunction "3_3") (pintype "passive"))
    )
    (net (code "68") (name "unconnected-(PR2-Pad3)") (class "Default")
      (node (ref "PR2") (pin "3") (pinfunction "3_3") (pintype "passive"))
    )
    (net (code "69") (name "unconnected-(PR3-Pad3)") (class "Default")
      (node (ref "PR3") (pin "3") (pinfunction "3_3") (pintype "passive"))
    )
    (net (code "70") (name "unconnected-(PR4-Pad3)") (class "Default")
      (node (ref "PR4") (pin "3") (pinfunction "3_3") (pintype "passive"))
    )
    (net (code "71") (name "unconnected-(PR5-Pad3)") (class "Default")
      (node (ref "PR5") (pin "3") (pinfunction "3_3") (pintype "passive"))
    )
    (net (code "72") (name "unconnected-(PR6-Pad3)") (class "Default")
      (node (ref "PR6") (pin "3") (pinfunction "3_3") (pintype "passive"))
    )
  )
)
